# Jafar-SE_-_EasyEDA_-_Schematic_Export.net
KiCad netlist of a schematic drawn in EasyEDA
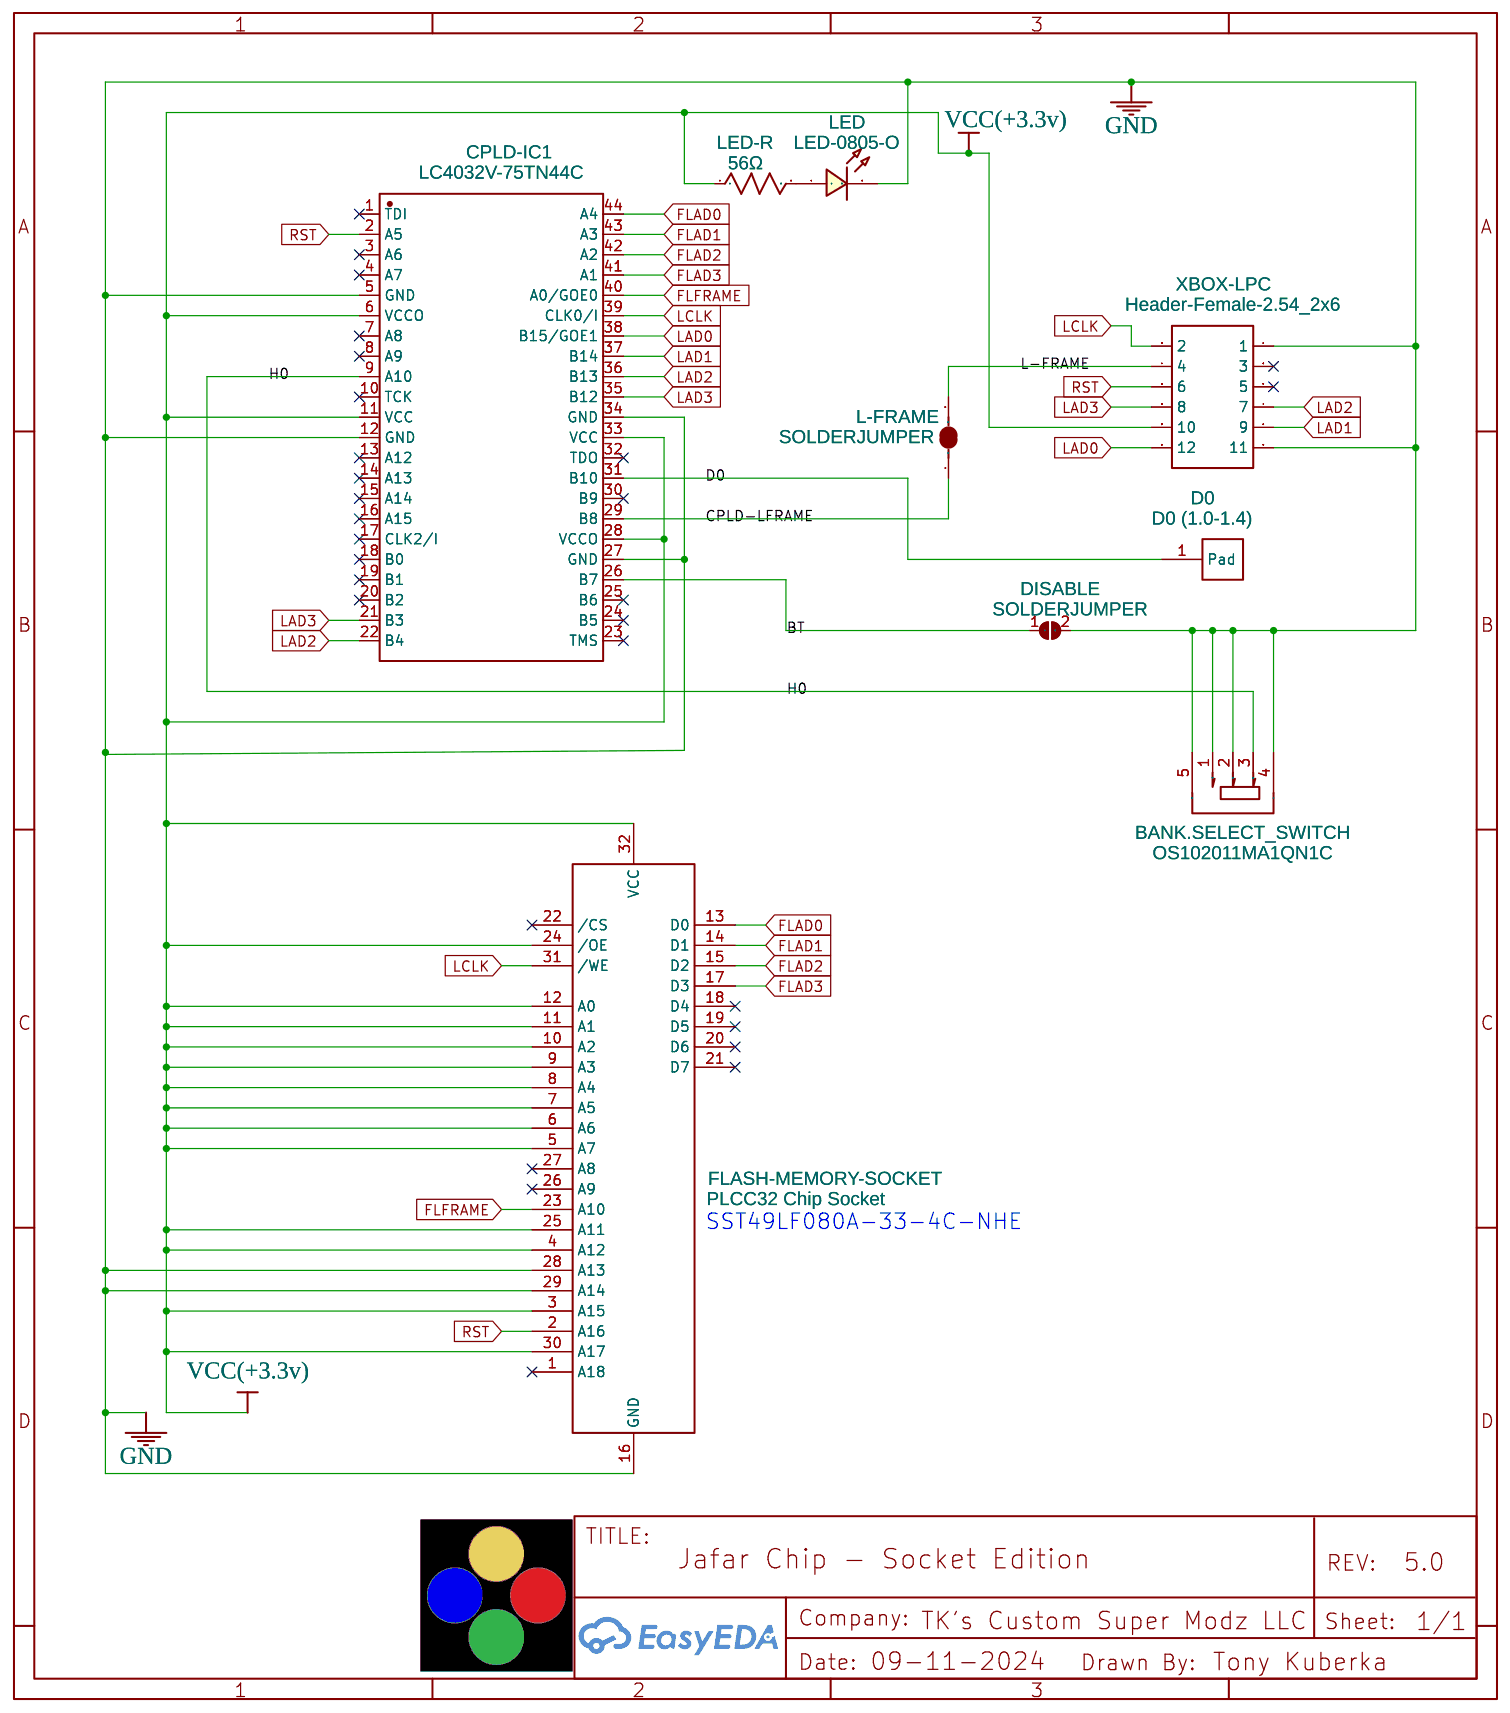
[diagram p0: schematic sheet]

(export (version "E")
  (design (tool "Eeschema 10.0.6"))
  (components
    (comp (ref "BANK.SELECT_SWITCH")
      (value "OS102011MA1QN1C")
      (fields (field (name "Manufacturer") "C&K"))
      (libsource (lib "") (part "OS102011MA1QN1C"))
    )
    (comp (ref "CPLD-IC1")
      (value "LC4032V-75TN44C")
      (fields (field (name "Manufacturer") "LATTICE(莱迪思)"))
      (libsource (lib "") (part "LC4032V-75TN44C"))
    )
    (comp (ref "D0") (value "D0 (1.0-1.4)") (libsource (lib "") (part "SOLDER PAD")))
    (comp (ref "DISABLE")
      (value "SOLDERJUMPER")
      (fields (field (name "Manufacturer Part") "DNP"))
      (libsource (lib "") (part "Solder bridge"))
    )
    (comp (ref "FLASH-MEMORY-SOCKET")
      (value "PLCC32 Chip Socket")
      (fields
        (field (name "Manufacturer Part") "SST39VF040-70-4C-NHE")
        (field (name "Manufacturer") "Microchip Technology")
      )
      (libsource (lib "") (part "SST39VF040-70-4C-NHE"))
    )
    (comp (ref "L-FRAME") (value "SOLDERJUMPER") (libsource (lib "") (part "SOLDERJUMPER-OLDNC2")))
    (comp (ref "LED")
      (value "LED-0805-O")
      (fields
        (field (name "Manufacturer Part") "SZYY0805O")
        (field (name "Manufacturer") "Yongyu Photoelectric")
      )
      (libsource (lib "") (part "LED-0805-ORANGE"))
    )
    (comp (ref "LED-R") (value "56Ω") (libsource (lib "") (part "R_0805_US")))
    (comp (ref "XBOX-LPC")
      (value "Header-Female-2.54_2x6")
      (fields (field (name "Manufacturer Part") "2.54-2*6P母") (field (name "Manufacturer") "BOOMELE(博穆精密)"))
      (libsource (lib "") (part "Header-Female-2.54_2x6"))
    )
  )
  (nets
    (net (code "1") (name "/BT") (class "Default")
      (node (ref "CPLD-IC1") (pin "26") (pinfunction "B7_26") (pintype "unspecified"))
      (node (ref "DISABLE") (pin "1") (pinfunction "A_1") (pintype "unspecified"))
    )
    (net (code "2") (name "/CPLD-LFRAME") (class "Default")
      (node (ref "CPLD-IC1") (pin "29") (pinfunction "B8_29") (pintype "unspecified"))
      (node (ref "L-FRAME") (pin "1") (pinfunction "1_1") (pintype "unspecified"))
    )
    (net (code "3") (name "/D0") (class "Default")
      (node (ref "CPLD-IC1") (pin "31") (pinfunction "B10_31") (pintype "unspecified"))
      (node (ref "D0") (pin "1") (pinfunction "Pad_1") (pintype "unspecified"))
    )
    (net (code "4") (name "/H0") (class "Default")
      (node (ref "BANK.SELECT_SWITCH") (pin "3") (pinfunction "3_3") (pintype "unspecified"))
      (node (ref "CPLD-IC1") (pin "9") (pinfunction "A10_9") (pintype "unspecified"))
    )
    (net (code "5") (name "/L-FRAME") (class "Default")
      (node (ref "L-FRAME") (pin "2") (pinfunction "2_2") (pintype "unspecified"))
      (node (ref "XBOX-LPC") (pin "4") (pinfunction "4_4") (pintype "input"))
    )
    (net (code "6") (name "FLAD0") (class "Default")
      (node (ref "CPLD-IC1") (pin "44") (pinfunction "A4_44") (pintype "unspecified"))
      (node (ref "FLASH-MEMORY-SOCKET") (pin "13") (pinfunction "D0_13") (pintype "unspecified"))
    )
    (net (code "7") (name "FLAD1") (class "Default")
      (node (ref "CPLD-IC1") (pin "43") (pinfunction "A3_43") (pintype "unspecified"))
      (node (ref "FLASH-MEMORY-SOCKET") (pin "14") (pinfunction "D1_14") (pintype "unspecified"))
    )
    (net (code "8") (name "FLAD2") (class "Default")
      (node (ref "CPLD-IC1") (pin "42") (pinfunction "A2_42") (pintype "unspecified"))
      (node (ref "FLASH-MEMORY-SOCKET") (pin "15") (pinfunction "D2_15") (pintype "unspecified"))
    )
    (net (code "9") (name "FLAD3") (class "Default")
      (node (ref "CPLD-IC1") (pin "41") (pinfunction "A1_41") (pintype "unspecified"))
      (node (ref "FLASH-MEMORY-SOCKET") (pin "17") (pinfunction "D3_17") (pintype "unspecified"))
    )
    (net (code "10") (name "FLFRAME") (class "Default")
      (node (ref "CPLD-IC1") (pin "40") (pinfunction "A0/GOE0_40") (pintype "unspecified"))
      (node (ref "FLASH-MEMORY-SOCKET") (pin "23") (pinfunction "A10_23") (pintype "unspecified"))
    )
    (net (code "11") (name "GND") (class "Default")
      (node (ref "BANK.SELECT_SWITCH") (pin "1") (pinfunction "1_1") (pintype "unspecified"))
      (node (ref "BANK.SELECT_SWITCH") (pin "2") (pinfunction "2_2") (pintype "unspecified"))
      (node (ref "BANK.SELECT_SWITCH") (pin "4") (pinfunction "4_4") (pintype "unspecified"))
      (node (ref "BANK.SELECT_SWITCH") (pin "5") (pinfunction "5_5") (pintype "unspecified"))
      (node (ref "CPLD-IC1") (pin "12") (pinfunction "GND_12") (pintype "unspecified"))
      (node (ref "CPLD-IC1") (pin "27") (pinfunction "GND_27") (pintype "unspecified"))
      (node (ref "CPLD-IC1") (pin "34") (pinfunction "GND_34") (pintype "unspecified"))
      (node (ref "CPLD-IC1") (pin "5") (pinfunction "GND_5") (pintype "unspecified"))
      (node (ref "DISABLE") (pin "2") (pinfunction "B_2") (pintype "unspecified"))
      (node (ref "FLASH-MEMORY-SOCKET") (pin "16") (pinfunction "GND_16") (pintype "unspecified"))
      (node (ref "FLASH-MEMORY-SOCKET") (pin "28") (pinfunction "A13_28") (pintype "unspecified"))
      (node (ref "FLASH-MEMORY-SOCKET") (pin "29") (pinfunction "A14_29") (pintype "unspecified"))
      (node (ref "LED") (pin "2") (pinfunction "2_2") (pintype "unspecified"))
      (node (ref "XBOX-LPC") (pin "1") (pinfunction "1_1") (pintype "input"))
      (node (ref "XBOX-LPC") (pin "11") (pinfunction "11_11") (pintype "input"))
    )
    (net (code "12") (name "LAD0") (class "Default")
      (node (ref "CPLD-IC1") (pin "38") (pinfunction "B15/GOE1_38") (pintype "unspecified"))
      (node (ref "XBOX-LPC") (pin "12") (pinfunction "12_12") (pintype "input"))
    )
    (net (code "13") (name "LAD1") (class "Default")
      (node (ref "CPLD-IC1") (pin "37") (pinfunction "B14_37") (pintype "unspecified"))
      (node (ref "XBOX-LPC") (pin "9") (pinfunction "9_9") (pintype "input"))
    )
    (net (code "14") (name "LAD2") (class "Default")
      (node (ref "CPLD-IC1") (pin "22") (pinfunction "B4_22") (pintype "unspecified"))
      (node (ref "CPLD-IC1") (pin "36") (pinfunction "B13_36") (pintype "unspecified"))
      (node (ref "XBOX-LPC") (pin "7") (pinfunction "7_7") (pintype "input"))
    )
    (net (code "15") (name "LAD3") (class "Default")
      (node (ref "CPLD-IC1") (pin "21") (pinfunction "B3_21") (pintype "unspecified"))
      (node (ref "CPLD-IC1") (pin "35") (pinfunction "B12_35") (pintype "unspecified"))
      (node (ref "XBOX-LPC") (pin "8") (pinfunction "8_8") (pintype "input"))
    )
    (net (code "16") (name "LCLK") (class "Default")
      (node (ref "CPLD-IC1") (pin "39") (pinfunction "CLK0/I_39") (pintype "unspecified"))
      (node (ref "FLASH-MEMORY-SOCKET") (pin "31") (pinfunction "/WE_31") (pintype "unspecified"))
      (node (ref "XBOX-LPC") (pin "2") (pinfunction "2_2") (pintype "input"))
    )
    (net (code "17") (name "Net-(LED-Pad1)") (class "Default")
      (node (ref "LED") (pin "1") (pinfunction "1_1") (pintype "unspecified"))
      (node (ref "LED-R") (pin "2") (pinfunction "2_2") (pintype "unspecified"))
    )
    (net (code "18") (name "RST") (class "Default")
      (node (ref "CPLD-IC1") (pin "2") (pinfunction "A5_2") (pintype "unspecified"))
      (node (ref "FLASH-MEMORY-SOCKET") (pin "2") (pinfunction "A16_2") (pintype "unspecified"))
      (node (ref "XBOX-LPC") (pin "6") (pinfunction "6_6") (pintype "input"))
    )
    (net (code "19") (name "VCC(+3.3v)") (class "Default")
      (node (ref "CPLD-IC1") (pin "11") (pinfunction "VCC_11") (pintype "unspecified"))
      (node (ref "CPLD-IC1") (pin "28") (pinfunction "VCCO_28") (pintype "unspecified"))
      (node (ref "CPLD-IC1") (pin "33") (pinfunction "VCC_33") (pintype "unspecified"))
      (node (ref "CPLD-IC1") (pin "6") (pinfunction "VCCO_6") (pintype "unspecified"))
      (node (ref "FLASH-MEMORY-SOCKET") (pin "10") (pinfunction "A2_10") (pintype "unspecified"))
      (node (ref "FLASH-MEMORY-SOCKET") (pin "11") (pinfunction "A1_11") (pintype "unspecified"))
      (node (ref "FLASH-MEMORY-SOCKET") (pin "12") (pinfunction "A0_12") (pintype "unspecified"))
      (node (ref "FLASH-MEMORY-SOCKET") (pin "24") (pinfunction "/OE_24") (pintype "unspecified"))
      (node (ref "FLASH-MEMORY-SOCKET") (pin "25") (pinfunction "A11_25") (pintype "unspecified"))
      (node (ref "FLASH-MEMORY-SOCKET") (pin "3") (pinfunction "A15_3") (pintype "unspecified"))
      (node (ref "FLASH-MEMORY-SOCKET") (pin "30") (pinfunction "A17_30") (pintype "unspecified"))
      (node (ref "FLASH-MEMORY-SOCKET") (pin "32") (pinfunction "VCC_32") (pintype "unspecified"))
      (node (ref "FLASH-MEMORY-SOCKET") (pin "4") (pinfunction "A12_4") (pintype "unspecified"))
      (node (ref "FLASH-MEMORY-SOCKET") (pin "5") (pinfunction "A7_5") (pintype "unspecified"))
      (node (ref "FLASH-MEMORY-SOCKET") (pin "6") (pinfunction "A6_6") (pintype "unspecified"))
      (node (ref "FLASH-MEMORY-SOCKET") (pin "7") (pinfunction "A5_7") (pintype "unspecified"))
      (node (ref "FLASH-MEMORY-SOCKET") (pin "8") (pinfunction "A4_8") (pintype "unspecified"))
      (node (ref "FLASH-MEMORY-SOCKET") (pin "9") (pinfunction "A3_9") (pintype "unspecified"))
      (node (ref "LED-R") (pin "1") (pinfunction "1_1") (pintype "unspecified"))
      (node (ref "XBOX-LPC") (pin "10") (pinfunction "10_10") (pintype "input"))
    )
    (net (code "20") (name "unconnected-(CPLD-IC1-A6-Pad3)") (class "Default")
      (node (ref "CPLD-IC1") (pin "3") (pinfunction "A6_3") (pintype "unspecified+no_connect"))
    )
    (net (code "21") (name "unconnected-(CPLD-IC1-A7-Pad4)") (class "Default")
      (node (ref "CPLD-IC1") (pin "4") (pinfunction "A7_4") (pintype "unspecified+no_connect"))
    )
    (net (code "22") (name "unconnected-(CPLD-IC1-A8-Pad7)") (class "Default")
      (node (ref "CPLD-IC1") (pin "7") (pinfunction "A8_7") (pintype "unspecified+no_connect"))
    )
    (net (code "23") (name "unconnected-(CPLD-IC1-A9-Pad8)") (class "Default")
      (node (ref "CPLD-IC1") (pin "8") (pinfunction "A9_8") (pintype "unspecified+no_connect"))
    )
    (net (code "24") (name "unconnected-(CPLD-IC1-A12-Pad13)") (class "Default")
      (node (ref "CPLD-IC1") (pin "13") (pinfunction "A12_13") (pintype "unspecified+no_connect"))
    )
    (net (code "25") (name "unconnected-(CPLD-IC1-A13-Pad14)") (class "Default")
      (node (ref "CPLD-IC1") (pin "14") (pinfunction "A13_14") (pintype "unspecified+no_connect"))
    )
    (net (code "26") (name "unconnected-(CPLD-IC1-A14-Pad15)") (class "Default")
      (node (ref "CPLD-IC1") (pin "15") (pinfunction "A14_15") (pintype "unspecified+no_connect"))
    )
    (net (code "27") (name "unconnected-(CPLD-IC1-A15-Pad16)") (class "Default")
      (node (ref "CPLD-IC1") (pin "16") (pinfunction "A15_16") (pintype "unspecified+no_connect"))
    )
    (net (code "28") (name "unconnected-(CPLD-IC1-B0-Pad18)") (class "Default")
      (node (ref "CPLD-IC1") (pin "18") (pinfunction "B0_18") (pintype "unspecified+no_connect"))
    )
    (net (code "29") (name "unconnected-(CPLD-IC1-B1-Pad19)") (class "Default")
      (node (ref "CPLD-IC1") (pin "19") (pinfunction "B1_19") (pintype "unspecified+no_connect"))
    )
    (net (code "30") (name "unconnected-(CPLD-IC1-B2-Pad20)") (class "Default")
      (node (ref "CPLD-IC1") (pin "20") (pinfunction "B2_20") (pintype "unspecified+no_connect"))
    )
    (net (code "31") (name "unconnected-(CPLD-IC1-B5-Pad24)") (class "Default")
      (node (ref "CPLD-IC1") (pin "24") (pinfunction "B5_24") (pintype "unspecified+no_connect"))
    )
    (net (code "32") (name "unconnected-(CPLD-IC1-B6-Pad25)") (class "Default")
      (node (ref "CPLD-IC1") (pin "25") (pinfunction "B6_25") (pintype "unspecified+no_connect"))
    )
    (net (code "33") (name "unconnected-(CPLD-IC1-B9-Pad30)") (class "Default")
      (node (ref "CPLD-IC1") (pin "30") (pinfunction "B9_30") (pintype "unspecified+no_connect"))
    )
    (net (code "34") (name "unconnected-(CPLD-IC1-CLK2{slash}I-Pad17)") (class "Default")
      (node (ref "CPLD-IC1") (pin "17") (pinfunction "CLK2/I_17") (pintype "unspecified+no_connect"))
    )
    (net (code "35") (name "unconnected-(CPLD-IC1-TCK-Pad10)") (class "Default")
      (node (ref "CPLD-IC1") (pin "10") (pinfunction "TCK_10") (pintype "unspecified+no_connect"))
    )
    (net (code "36") (name "unconnected-(CPLD-IC1-TDI-Pad1)") (class "Default")
      (node (ref "CPLD-IC1") (pin "1") (pinfunction "TDI_1") (pintype "unspecified+no_connect"))
    )
    (net (code "37") (name "unconnected-(CPLD-IC1-TDO-Pad32)") (class "Default")
      (node (ref "CPLD-IC1") (pin "32") (pinfunction "TDO_32") (pintype "unspecified+no_connect"))
    )
    (net (code "38") (name "unconnected-(CPLD-IC1-TMS-Pad23)") (class "Default")
      (node (ref "CPLD-IC1") (pin "23") (pinfunction "TMS_23") (pintype "unspecified+no_connect"))
    )
    (net (code "39") (name "unconnected-(FLASH-MEMORY-SOCKET-A8-Pad27)") (class "Default")
      (node (ref "FLASH-MEMORY-SOCKET") (pin "27") (pinfunction "A8_27") (pintype "unspecified+no_connect"))
    )
    (net (code "40") (name "unconnected-(FLASH-MEMORY-SOCKET-A9-Pad26)") (class "Default")
      (node (ref "FLASH-MEMORY-SOCKET") (pin "26") (pinfunction "A9_26") (pintype "unspecified+no_connect"))
    )
    (net (code "41") (name "unconnected-(FLASH-MEMORY-SOCKET-A18-Pad1)") (class "Default")
      (node (ref "FLASH-MEMORY-SOCKET") (pin "1") (pinfunction "A18_1") (pintype "unspecified+no_connect"))
    )
    (net (code "42") (name "unconnected-(FLASH-MEMORY-SOCKET-D4-Pad18)") (class "Default")
      (node (ref "FLASH-MEMORY-SOCKET") (pin "18") (pinfunction "D4_18") (pintype "unspecified+no_connect"))
    )
    (net (code "43") (name "unconnected-(FLASH-MEMORY-SOCKET-D5-Pad19)") (class "Default")
      (node (ref "FLASH-MEMORY-SOCKET") (pin "19") (pinfunction "D5_19") (pintype "unspecified+no_connect"))
    )
    (net (code "44") (name "unconnected-(FLASH-MEMORY-SOCKET-D6-Pad20)") (class "Default")
      (node (ref "FLASH-MEMORY-SOCKET") (pin "20") (pinfunction "D6_20") (pintype "unspecified+no_connect"))
    )
    (net (code "45") (name "unconnected-(FLASH-MEMORY-SOCKET-D7-Pad21)") (class "Default")
      (node (ref "FLASH-MEMORY-SOCKET") (pin "21") (pinfunction "D7_21") (pintype "unspecified+no_connect"))
    )
    (net (code "46") (name "unconnected-(FLASH-MEMORY-SOCKET-{slash}CS-Pad22)") (class "Default")
      (node (ref "FLASH-MEMORY-SOCKET") (pin "22") (pinfunction "/CS_22") (pintype "unspecified+no_connect"))
    )
    (net (code "47") (name "unconnected-(XBOX-LPC-Pad3)") (class "Default")
      (node (ref "XBOX-LPC") (pin "3") (pinfunction "3_3") (pintype "input+no_connect"))
    )
    (net (code "48") (name "unconnected-(XBOX-LPC-Pad5)") (class "Default")
      (node (ref "XBOX-LPC") (pin "5") (pinfunction "5_5") (pintype "input+no_connect"))
    )
  )
)
